# Napajanje_2.net
KiCad netlist of a schematic drawn in Altium Designer
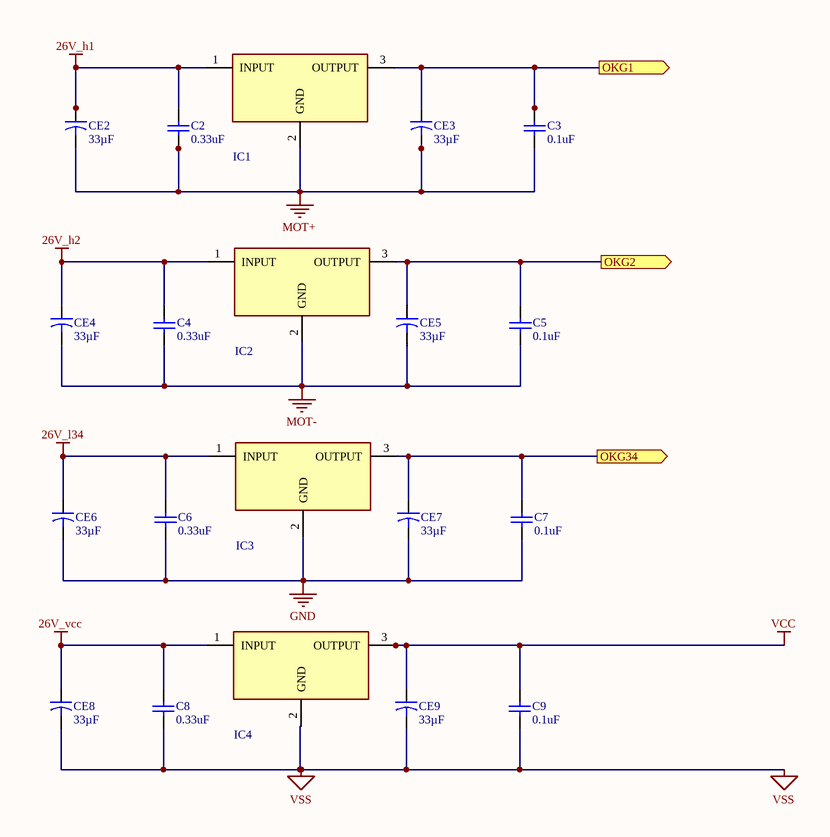
[diagram p0: Napajanje_2.SchDoc]

(export (version "E")
  (design (tool "Eeschema 10.0.6"))
  (components
    (comp (ref "C2")
      (value "0.33uF")
      (footprint "CAP3, 0.33uF, 50V")
      (description "CER 0.33uF, 50V")
      (fields
        (field (name "DIGI-KEY PART NUMBER") "1C20Z5U334M050B-ND")
        (field (name "MANUFACTURER") "Vishay BC Components")
      )
      (libsource (lib "Coper") (part "Cap3"))
    )
    (comp (ref "C3")
      (value "0.1uF")
      (footprint "CAP4, 0.1uF, 50V")
      (description "CER 0.1uF, 50V")
      (fields
        (field (name "DIGI-KEY PART NUMBER") "BC1160TR-ND")
        (field (name "MANUFACTURER") "Vishay BC Components")
      )
      (libsource (lib "Coper") (part "Cap4"))
    )
    (comp (ref "C4")
      (value "0.33uF")
      (footprint "CAP3, 0.33uF, 50V")
      (description "CER 0.33uF, 50V")
      (fields
        (field (name "DIGI-KEY PART NUMBER") "1C20Z5U334M050B-ND")
        (field (name "MANUFACTURER") "Vishay BC Components")
      )
      (libsource (lib "Coper") (part "Cap3"))
    )
    (comp (ref "C5")
      (value "0.1uF")
      (footprint "CAP4, 0.1uF, 50V")
      (description "CER 0.1uF, 50V")
      (fields
        (field (name "DIGI-KEY PART NUMBER") "BC1160TR-ND")
        (field (name "MANUFACTURER") "Vishay BC Components")
      )
      (libsource (lib "Coper") (part "Cap4"))
    )
    (comp (ref "C6")
      (value "0.33uF")
      (footprint "CAP3, 0.33uF, 50V")
      (description "CER 0.33uF, 50V")
      (fields
        (field (name "DIGI-KEY PART NUMBER") "1C20Z5U334M050B-ND")
        (field (name "MANUFACTURER") "Vishay BC Components")
      )
      (libsource (lib "Coper") (part "Cap3"))
    )
    (comp (ref "C7")
      (value "0.1uF")
      (footprint "CAP4, 0.1uF, 50V")
      (description "CER 0.1uF, 50V")
      (fields
        (field (name "DIGI-KEY PART NUMBER") "BC1160TR-ND")
        (field (name "MANUFACTURER") "Vishay BC Components")
      )
      (libsource (lib "Coper") (part "Cap4"))
    )
    (comp (ref "C8")
      (value "0.33uF")
      (footprint "CAP3, 0.33uF, 50V")
      (description "CER 0.33uF, 50V")
      (fields
        (field (name "DIGI-KEY PART NUMBER") "1C20Z5U334M050B-ND")
        (field (name "MANUFACTURER") "Vishay BC Components")
      )
      (libsource (lib "Coper") (part "Cap3"))
    )
    (comp (ref "C9")
      (value "0.1uF")
      (footprint "CAP4, 0.1uF, 50V")
      (description "CER 0.1uF, 50V")
      (fields
        (field (name "DIGI-KEY PART NUMBER") "BC1160TR-ND")
        (field (name "MANUFACTURER") "Vishay BC Components")
      )
      (libsource (lib "Coper") (part "Cap4"))
    )
    (comp (ref "CE2")
      (value "33µF")
      (footprint "CAP1 33uF, 35V")
      (description "ALU 33uF, 35V")
      (fields (field (name "DIGI-KEY PART NUMBER") "399-6575-ND") (field (name "MANUFACTURER") "KEMET"))
      (libsource (lib "Coper") (part "Cap1"))
    )
    (comp (ref "CE3")
      (value "33µF")
      (footprint "CAP1 33uF, 35V")
      (description "ALU 33uF, 35V")
      (fields (field (name "DIGI-KEY PART NUMBER") "399-6575-ND") (field (name "MANUFACTURER") "KEMET"))
      (libsource (lib "Coper") (part "Cap1"))
    )
    (comp (ref "CE4")
      (value "33µF")
      (footprint "CAP1 33uF, 35V")
      (description "ALU 33uF, 35V")
      (fields (field (name "DIGI-KEY PART NUMBER") "399-6575-ND") (field (name "MANUFACTURER") "KEMET"))
      (libsource (lib "Coper") (part "Cap1"))
    )
    (comp (ref "CE5")
      (value "33µF")
      (footprint "CAP1 33uF, 35V")
      (description "ALU 33uF, 35V")
      (fields (field (name "DIGI-KEY PART NUMBER") "399-6575-ND") (field (name "MANUFACTURER") "KEMET"))
      (libsource (lib "Coper") (part "Cap1"))
    )
    (comp (ref "CE6")
      (value "33µF")
      (footprint "CAP1 33uF, 35V")
      (description "ALU 33uF, 35V")
      (fields (field (name "DIGI-KEY PART NUMBER") "399-6575-ND") (field (name "MANUFACTURER") "KEMET"))
      (libsource (lib "Coper") (part "Cap1"))
    )
    (comp (ref "CE7")
      (value "33µF")
      (footprint "CAP1 33uF, 35V")
      (description "ALU 33uF, 35V")
      (fields (field (name "DIGI-KEY PART NUMBER") "399-6575-ND") (field (name "MANUFACTURER") "KEMET"))
      (libsource (lib "Coper") (part "Cap1"))
    )
    (comp (ref "CE8")
      (value "33µF")
      (footprint "CAP1 33uF, 35V")
      (description "ALU 33uF, 35V")
      (fields (field (name "DIGI-KEY PART NUMBER") "399-6575-ND") (field (name "MANUFACTURER") "KEMET"))
      (libsource (lib "Coper") (part "Cap1"))
    )
    (comp (ref "CE9")
      (value "33µF")
      (footprint "CAP1 33uF, 35V")
      (description "ALU 33uF, 35V")
      (fields (field (name "DIGI-KEY PART NUMBER") "399-6575-ND") (field (name "MANUFACTURER") "KEMET"))
      (libsource (lib "Coper") (part "Cap1"))
    )
    (comp (ref "IC1")
      (value "512-LM7812ACT")
      (footprint "LM7812ACT, 1A")
      (description "LM7812ACT, 1A")
      (fields (field (name "MANUFACTURER_PART_NUMBER") "LM7812ACT") (field (name "RS PART NUMBER") "8062839"))
      (libsource (lib "Coper") (part "IC2"))
    )
    (comp (ref "IC2")
      (value "512-LM7812ACT")
      (footprint "LM7812ACT, 1A")
      (description "LM7812ACT, 1A")
      (fields (field (name "MANUFACTURER_PART_NUMBER") "LM7812ACT") (field (name "RS PART NUMBER") "8062839"))
      (libsource (lib "Coper") (part "IC2"))
    )
    (comp (ref "IC3")
      (value "512-LM7812ACT")
      (footprint "LM7812ACT, 1A")
      (description "LM7812ACT, 1A")
      (fields (field (name "MANUFACTURER_PART_NUMBER") "LM7812ACT") (field (name "RS PART NUMBER") "8062839"))
      (libsource (lib "Coper") (part "IC2"))
    )
    (comp (ref "IC4")
      (value "LM7805ACT")
      (footprint "LM7805ACT, 1A")
      (description "LM7805ACT, 1A")
      (fields (field (name "MOUSER PART NUMBER") "512-LM7805ACT") (field (name "RS PART NUMBER") "8062839"))
      (libsource (lib "Coper") (part "IC1"))
    )
  )
  (nets
    (net (code "1") (name "/OKG1") (class "Default")
      (node (ref "C3") (pin "2") (pinfunction "2_2") (pintype "passive"))
      (node (ref "CE3") (pin "1") (pinfunction "1_1") (pintype "passive"))
      (node (ref "IC1") (pin "3") (pinfunction "OUTPUT_3") (pintype "passive"))
    )
    (net (code "2") (name "/OKG2") (class "Default")
      (node (ref "C5") (pin "2") (pinfunction "2_2") (pintype "passive"))
      (node (ref "CE5") (pin "1") (pinfunction "1_1") (pintype "passive"))
      (node (ref "IC2") (pin "3") (pinfunction "OUTPUT_3") (pintype "passive"))
    )
    (net (code "3") (name "/OKG34") (class "Default")
      (node (ref "C7") (pin "2") (pinfunction "2_2") (pintype "passive"))
      (node (ref "CE7") (pin "1") (pinfunction "1_1") (pintype "passive"))
      (node (ref "IC3") (pin "3") (pinfunction "OUTPUT_3") (pintype "passive"))
    )
    (net (code "4") (name "26V_h1") (class "Default")
      (node (ref "C2") (pin "2") (pinfunction "2_2") (pintype "passive"))
      (node (ref "CE2") (pin "1") (pinfunction "1_1") (pintype "passive"))
      (node (ref "IC1") (pin "1") (pinfunction "INPUT_1") (pintype "passive"))
    )
    (net (code "5") (name "26V_h2") (class "Default")
      (node (ref "C4") (pin "2") (pinfunction "2_2") (pintype "passive"))
      (node (ref "CE4") (pin "1") (pinfunction "1_1") (pintype "passive"))
      (node (ref "IC2") (pin "1") (pinfunction "INPUT_1") (pintype "passive"))
    )
    (net (code "6") (name "26V_l34") (class "Default")
      (node (ref "C6") (pin "2") (pinfunction "2_2") (pintype "passive"))
      (node (ref "CE6") (pin "1") (pinfunction "1_1") (pintype "passive"))
      (node (ref "IC3") (pin "1") (pinfunction "INPUT_1") (pintype "passive"))
    )
    (net (code "7") (name "26V_vcc") (class "Default")
      (node (ref "C8") (pin "2") (pinfunction "2_2") (pintype "passive"))
      (node (ref "CE8") (pin "1") (pinfunction "1_1") (pintype "passive"))
      (node (ref "IC4") (pin "1") (pinfunction "INPUT_1") (pintype "passive"))
    )
    (net (code "8") (name "GND") (class "Default")
      (node (ref "C6") (pin "1") (pinfunction "1_1") (pintype "passive"))
      (node (ref "C7") (pin "1") (pinfunction "1_1") (pintype "passive"))
      (node (ref "CE6") (pin "2") (pinfunction "2_2") (pintype "passive"))
      (node (ref "CE7") (pin "2") (pinfunction "2_2") (pintype "passive"))
      (node (ref "IC3") (pin "2") (pinfunction "GND_2") (pintype "passive"))
    )
    (net (code "9") (name "MOT+") (class "Default")
      (node (ref "C2") (pin "1") (pinfunction "1_1") (pintype "passive"))
      (node (ref "C3") (pin "1") (pinfunction "1_1") (pintype "passive"))
      (node (ref "CE2") (pin "2") (pinfunction "2_2") (pintype "passive"))
      (node (ref "CE3") (pin "2") (pinfunction "2_2") (pintype "passive"))
      (node (ref "IC1") (pin "2") (pinfunction "GND_2") (pintype "passive"))
    )
    (net (code "10") (name "MOT-") (class "Default")
      (node (ref "C4") (pin "1") (pinfunction "1_1") (pintype "passive"))
      (node (ref "C5") (pin "1") (pinfunction "1_1") (pintype "passive"))
      (node (ref "CE4") (pin "2") (pinfunction "2_2") (pintype "passive"))
      (node (ref "CE5") (pin "2") (pinfunction "2_2") (pintype "passive"))
      (node (ref "IC2") (pin "2") (pinfunction "GND_2") (pintype "passive"))
    )
    (net (code "11") (name "VCC") (class "Default")
      (node (ref "C9") (pin "2") (pinfunction "2_2") (pintype "passive"))
      (node (ref "CE9") (pin "1") (pinfunction "1_1") (pintype "passive"))
      (node (ref "IC4") (pin "3") (pinfunction "OUTPUT_3") (pintype "passive"))
    )
    (net (code "12") (name "VSS") (class "Default")
      (node (ref "C8") (pin "1") (pinfunction "1_1") (pintype "passive"))
      (node (ref "C9") (pin "1") (pinfunction "1_1") (pintype "passive"))
      (node (ref "CE8") (pin "2") (pinfunction "2_2") (pintype "passive"))
      (node (ref "CE9") (pin "2") (pinfunction "2_2") (pintype "passive"))
      (node (ref "IC4") (pin "2") (pinfunction "GND_2") (pintype "passive"))
    )
  )
)
